# ringmod.net
KiCad netlist of a schematic drawn in EAGLE
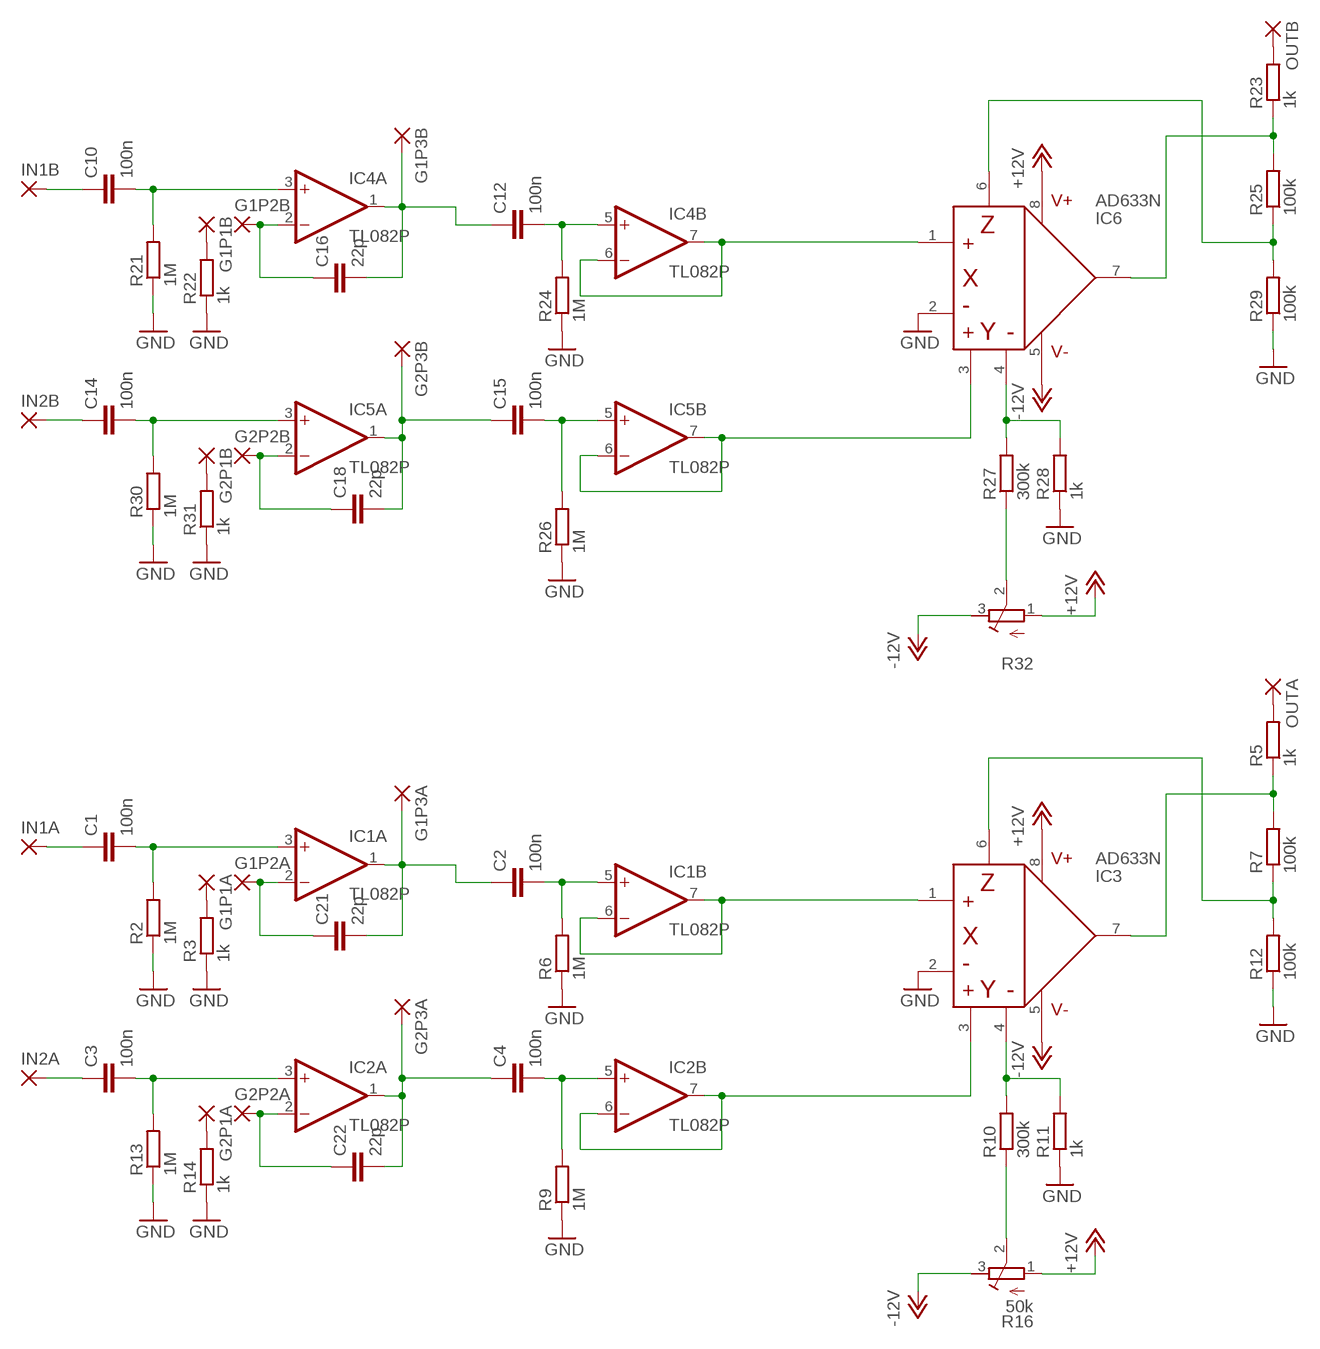
[diagram p0: schematic, sheet 1]
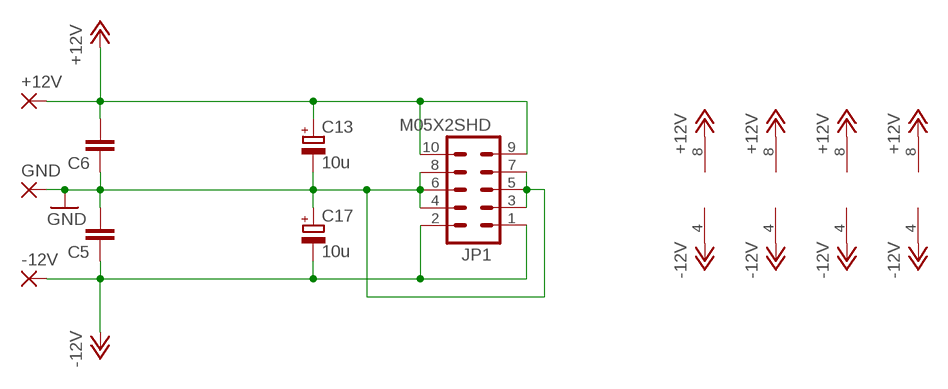
[diagram p1: schematic, sheet 2]

(export (version "E")
  (design (tool "Eeschema 10.0.6"))
  (components
    (comp (ref "C1")
      (value "100n")
      (footprint "eagle-import:C050-035X075")
      (libsource (lib "eagle-import") (part "C-EU050-035X075"))
    )
    (comp (ref "C2")
      (value "100n")
      (footprint "eagle-import:C050-035X075")
      (libsource (lib "eagle-import") (part "C-EU050-035X075"))
    )
    (comp (ref "C3")
      (value "100n")
      (footprint "eagle-import:C050-035X075")
      (libsource (lib "eagle-import") (part "C-EU050-035X075"))
    )
    (comp (ref "C4")
      (value "100n")
      (footprint "eagle-import:C050-035X075")
      (libsource (lib "eagle-import") (part "C-EU050-035X075"))
    )
    (comp (ref "C10")
      (value "100n")
      (footprint "eagle-import:C050-035X075")
      (libsource (lib "eagle-import") (part "C-EU050-035X075"))
    )
    (comp (ref "C12")
      (value "100n")
      (footprint "eagle-import:C050-035X075")
      (libsource (lib "eagle-import") (part "C-EU050-035X075"))
    )
    (comp (ref "C14")
      (value "100n")
      (footprint "eagle-import:C050-035X075")
      (libsource (lib "eagle-import") (part "C-EU050-035X075"))
    )
    (comp (ref "C15")
      (value "100n")
      (footprint "eagle-import:C050-035X075")
      (libsource (lib "eagle-import") (part "C-EU050-035X075"))
    )
    (comp (ref "C16")
      (value "22p")
      (footprint "eagle-import:C050-035X075")
      (libsource (lib "eagle-import") (part "C-EU050-035X075"))
    )
    (comp (ref "C18")
      (value "22p")
      (footprint "eagle-import:C050-035X075")
      (libsource (lib "eagle-import") (part "C-EU050-035X075"))
    )
    (comp (ref "C21")
      (value "22p")
      (footprint "eagle-import:C050-035X075")
      (libsource (lib "eagle-import") (part "C-EU050-035X075"))
    )
    (comp (ref "C22")
      (value "22p")
      (footprint "eagle-import:C050-035X075")
      (libsource (lib "eagle-import") (part "C-EU050-035X075"))
    )
    (comp (ref "G1P1A")
      (value "2,54/1,0")
      (footprint "eagle-import:2,54_1,0")
      (libsource (lib "eagle-import") (part "2,54/1,0"))
    )
    (comp (ref "G1P1B")
      (value "2,54/1,0")
      (footprint "eagle-import:2,54_1,0")
      (libsource (lib "eagle-import") (part "2,54/1,0"))
    )
    (comp (ref "G1P2A")
      (value "2,54/1,0")
      (footprint "eagle-import:2,54_1,0")
      (libsource (lib "eagle-import") (part "2,54/1,0"))
    )
    (comp (ref "G1P2B")
      (value "2,54/1,0")
      (footprint "eagle-import:2,54_1,0")
      (libsource (lib "eagle-import") (part "2,54/1,0"))
    )
    (comp (ref "G1P3A")
      (value "2,54/1,0")
      (footprint "eagle-import:2,54_1,0")
      (libsource (lib "eagle-import") (part "2,54/1,0"))
    )
    (comp (ref "G1P3B")
      (value "2,54/1,0")
      (footprint "eagle-import:2,54_1,0")
      (libsource (lib "eagle-import") (part "2,54/1,0"))
    )
    (comp (ref "G2P1A")
      (value "2,54/1,0")
      (footprint "eagle-import:2,54_1,0")
      (libsource (lib "eagle-import") (part "2,54/1,0"))
    )
    (comp (ref "G2P1B")
      (value "2,54/1,0")
      (footprint "eagle-import:2,54_1,0")
      (libsource (lib "eagle-import") (part "2,54/1,0"))
    )
    (comp (ref "G2P2A")
      (value "2,54/1,0")
      (footprint "eagle-import:2,54_1,0")
      (libsource (lib "eagle-import") (part "2,54/1,0"))
    )
    (comp (ref "G2P2B")
      (value "2,54/1,0")
      (footprint "eagle-import:2,54_1,0")
      (libsource (lib "eagle-import") (part "2,54/1,0"))
    )
    (comp (ref "G2P3A")
      (value "2,54/1,0")
      (footprint "eagle-import:2,54_1,0")
      (libsource (lib "eagle-import") (part "2,54/1,0"))
    )
    (comp (ref "G2P3B")
      (value "2,54/1,0")
      (footprint "eagle-import:2,54_1,0")
      (libsource (lib "eagle-import") (part "2,54/1,0"))
    )
    (comp (ref "IC1")
      (value "TL082P")
      (footprint "eagle-import:DIL08")
      (libsource (lib "eagle-import") (part "TL082P"))
    )
    (comp (ref "IC2")
      (value "TL082P")
      (footprint "eagle-import:DIL08")
      (libsource (lib "eagle-import") (part "TL082P"))
    )
    (comp (ref "IC3")
      (value "AD633N")
      (footprint "eagle-import:DIL08")
      (libsource (lib "eagle-import") (part "AD633N"))
    )
    (comp (ref "IC4")
      (value "TL082P")
      (footprint "eagle-import:DIL08")
      (libsource (lib "eagle-import") (part "TL082P"))
    )
    (comp (ref "IC5")
      (value "TL082P")
      (footprint "eagle-import:DIL08")
      (libsource (lib "eagle-import") (part "TL082P"))
    )
    (comp (ref "IC6")
      (value "AD633N")
      (footprint "eagle-import:DIL08")
      (libsource (lib "eagle-import") (part "AD633N"))
    )
    (comp (ref "IN1A")
      (value "2,54/1,0")
      (footprint "eagle-import:2,54_1,0")
      (libsource (lib "eagle-import") (part "2,54/1,0"))
    )
    (comp (ref "IN1B")
      (value "2,54/1,0")
      (footprint "eagle-import:2,54_1,0")
      (libsource (lib "eagle-import") (part "2,54/1,0"))
    )
    (comp (ref "IN2A")
      (value "2,54/1,0")
      (footprint "eagle-import:2,54_1,0")
      (libsource (lib "eagle-import") (part "2,54/1,0"))
    )
    (comp (ref "IN2B")
      (value "2,54/1,0")
      (footprint "eagle-import:2,54_1,0")
      (libsource (lib "eagle-import") (part "2,54/1,0"))
    )
    (comp (ref "OUTA")
      (value "2,54/1,0")
      (footprint "eagle-import:2,54_1,0")
      (libsource (lib "eagle-import") (part "2,54/1,0"))
    )
    (comp (ref "OUTB")
      (value "2,54/1,0")
      (footprint "eagle-import:2,54_1,0")
      (libsource (lib "eagle-import") (part "2,54/1,0"))
    )
    (comp (ref "R2")
      (value "1M")
      (footprint "eagle-import:0309_10")
      (libsource (lib "eagle-import") (part "R-EU_0309/10"))
    )
    (comp (ref "R3")
      (value "1k")
      (footprint "eagle-import:0309_10")
      (libsource (lib "eagle-import") (part "R-EU_0309/10"))
    )
    (comp (ref "R5")
      (value "1k")
      (footprint "eagle-import:0309_10")
      (libsource (lib "eagle-import") (part "R-EU_0309/10"))
    )
    (comp (ref "R6")
      (value "1M")
      (footprint "eagle-import:0309_10")
      (libsource (lib "eagle-import") (part "R-EU_0309/10"))
    )
    (comp (ref "R7")
      (value "100k")
      (footprint "eagle-import:0309_10")
      (libsource (lib "eagle-import") (part "R-EU_0309/10"))
    )
    (comp (ref "R9")
      (value "1M")
      (footprint "eagle-import:0309_10")
      (libsource (lib "eagle-import") (part "R-EU_0309/10"))
    )
    (comp (ref "R10")
      (value "300k")
      (footprint "eagle-import:0309_10")
      (libsource (lib "eagle-import") (part "R-EU_0309/10"))
    )
    (comp (ref "R11")
      (value "1k")
      (footprint "eagle-import:0309_10")
      (libsource (lib "eagle-import") (part "R-EU_0309/10"))
    )
    (comp (ref "R12")
      (value "100k")
      (footprint "eagle-import:0309_10")
      (libsource (lib "eagle-import") (part "R-EU_0309/10"))
    )
    (comp (ref "R13")
      (value "1M")
      (footprint "eagle-import:0309_10")
      (libsource (lib "eagle-import") (part "R-EU_0309/10"))
    )
    (comp (ref "R14")
      (value "1k")
      (footprint "eagle-import:0309_10")
      (libsource (lib "eagle-import") (part "R-EU_0309/10"))
    )
    (comp (ref "R16")
      (value "50k")
      (footprint "eagle-import:RTRIM64W")
      (libsource (lib "eagle-import") (part "R-TRIMM64W"))
    )
    (comp (ref "R21")
      (value "1M")
      (footprint "eagle-import:0309_10")
      (libsource (lib "eagle-import") (part "R-EU_0309/10"))
    )
    (comp (ref "R22")
      (value "1k")
      (footprint "eagle-import:0309_10")
      (libsource (lib "eagle-import") (part "R-EU_0309/10"))
    )
    (comp (ref "R23")
      (value "1k")
      (footprint "eagle-import:0309_10")
      (libsource (lib "eagle-import") (part "R-EU_0309/10"))
    )
    (comp (ref "R24")
      (value "1M")
      (footprint "eagle-import:0309_10")
      (libsource (lib "eagle-import") (part "R-EU_0309/10"))
    )
    (comp (ref "R25")
      (value "100k")
      (footprint "eagle-import:0309_10")
      (libsource (lib "eagle-import") (part "R-EU_0309/10"))
    )
    (comp (ref "R26")
      (value "1M")
      (footprint "eagle-import:0309_10")
      (libsource (lib "eagle-import") (part "R-EU_0309/10"))
    )
    (comp (ref "R27")
      (value "300k")
      (footprint "eagle-import:0309_10")
      (libsource (lib "eagle-import") (part "R-EU_0309/10"))
    )
    (comp (ref "R28")
      (value "1k")
      (footprint "eagle-import:0309_10")
      (libsource (lib "eagle-import") (part "R-EU_0309/10"))
    )
    (comp (ref "R29")
      (value "100k")
      (footprint "eagle-import:0309_10")
      (libsource (lib "eagle-import") (part "R-EU_0309/10"))
    )
    (comp (ref "R30")
      (value "1M")
      (footprint "eagle-import:0309_10")
      (libsource (lib "eagle-import") (part "R-EU_0309/10"))
    )
    (comp (ref "R31")
      (value "1k")
      (footprint "eagle-import:0309_10")
      (libsource (lib "eagle-import") (part "R-EU_0309/10"))
    )
    (comp (ref "R32")
      (value "R-TRIMM64W")
      (footprint "eagle-import:RTRIM64W")
      (libsource (lib "eagle-import") (part "R-TRIMM64W"))
    )
    (comp (ref "+12V")
      (value "2,54/1,0")
      (footprint "eagle-import:2,54_1,0")
      (libsource (lib "eagle-import") (part "2,54/1,0"))
    )
    (comp (ref "-12V")
      (value "2,54/1,0")
      (footprint "eagle-import:2,54_1,0")
      (libsource (lib "eagle-import") (part "2,54/1,0"))
    )
    (comp (ref "C5")
      (value "C-EU050-035X075")
      (footprint "eagle-import:C050-035X075")
      (libsource (lib "eagle-import") (part "C-EU050-035X075"))
    )
    (comp (ref "C6")
      (value "C-EU050-035X075")
      (footprint "eagle-import:C050-035X075")
      (libsource (lib "eagle-import") (part "C-EU050-035X075"))
    )
    (comp (ref "C13")
      (value "10u")
      (footprint "eagle-import:E3,5-8")
      (libsource (lib "eagle-import") (part "CPOL-EUE3.5-8"))
    )
    (comp (ref "C17")
      (value "10u")
      (footprint "eagle-import:E3,5-8")
      (libsource (lib "eagle-import") (part "CPOL-EUE3.5-8"))
    )
    (comp (ref "GND")
      (value "2,54/1,0")
      (footprint "eagle-import:2,54_1,0")
      (libsource (lib "eagle-import") (part "2,54/1,0"))
    )
    (comp (ref "JP1")
      (value "M05X2SHD")
      (footprint "eagle-import:2X5-SHROUDED")
      (libsource (lib "eagle-import") (part "M05X2SHD"))
    )
  )
  (nets
    (net (code "1") (name "+12V") (class "Default")
      (node (ref "+12V") (pin "1") (pinfunction "P_1") (pintype "passive"))
      (node (ref "C13") (pin "+") (pinfunction "+_+") (pintype "passive"))
      (node (ref "C6") (pin "2") (pinfunction "2_2") (pintype "passive"))
      (node (ref "IC1") (pin "8") (pinfunction "V+_8") (pintype "power_in"))
      (node (ref "IC2") (pin "8") (pinfunction "V+_8") (pintype "power_in"))
      (node (ref "IC3") (pin "8") (pinfunction "P$7_8") (pintype "power_in"))
      (node (ref "IC4") (pin "8") (pinfunction "V+_8") (pintype "power_in"))
      (node (ref "IC5") (pin "8") (pinfunction "V+_8") (pintype "power_in"))
      (node (ref "IC6") (pin "8") (pinfunction "P$7_8") (pintype "power_in"))
      (node (ref "JP1") (pin "10") (pinfunction "10_10") (pintype "passive"))
      (node (ref "JP1") (pin "9") (pinfunction "9_9") (pintype "passive"))
      (node (ref "R16") (pin "1") (pinfunction "A_1") (pintype "passive"))
      (node (ref "R32") (pin "1") (pinfunction "A_1") (pintype "passive"))
    )
    (net (code "2") (name "-12V") (class "Default")
      (node (ref "-12V") (pin "1") (pinfunction "P_1") (pintype "passive"))
      (node (ref "C17") (pin "-") (pinfunction "-_-") (pintype "passive"))
      (node (ref "C5") (pin "1") (pinfunction "1_1") (pintype "passive"))
      (node (ref "IC1") (pin "4") (pinfunction "V-_4") (pintype "power_in"))
      (node (ref "IC2") (pin "4") (pinfunction "V-_4") (pintype "power_in"))
      (node (ref "IC3") (pin "5") (pinfunction "P$8_5") (pintype "power_in"))
      (node (ref "IC4") (pin "4") (pinfunction "V-_4") (pintype "power_in"))
      (node (ref "IC5") (pin "4") (pinfunction "V-_4") (pintype "power_in"))
      (node (ref "IC6") (pin "5") (pinfunction "P$8_5") (pintype "power_in"))
      (node (ref "JP1") (pin "1") (pinfunction "1_1") (pintype "passive"))
      (node (ref "JP1") (pin "2") (pinfunction "2_2") (pintype "passive"))
      (node (ref "R16") (pin "3") (pinfunction "E_3") (pintype "passive"))
      (node (ref "R32") (pin "3") (pinfunction "E_3") (pintype "passive"))
    )
    (net (code "3") (name "GND") (class "Default")
      (node (ref "C13") (pin "-") (pinfunction "-_-") (pintype "passive"))
      (node (ref "C17") (pin "+") (pinfunction "+_+") (pintype "passive"))
      (node (ref "C5") (pin "2") (pinfunction "2_2") (pintype "passive"))
      (node (ref "C6") (pin "1") (pinfunction "1_1") (pintype "passive"))
      (node (ref "GND") (pin "1") (pinfunction "P_1") (pintype "passive"))
      (node (ref "IC3") (pin "2") (pinfunction "P$2_2") (pintype "bidirectional"))
      (node (ref "IC6") (pin "2") (pinfunction "P$2_2") (pintype "bidirectional"))
      (node (ref "JP1") (pin "3") (pinfunction "3_3") (pintype "passive"))
      (node (ref "JP1") (pin "4") (pinfunction "4_4") (pintype "passive"))
      (node (ref "JP1") (pin "5") (pinfunction "5_5") (pintype "passive"))
      (node (ref "JP1") (pin "6") (pinfunction "6_6") (pintype "passive"))
      (node (ref "JP1") (pin "7") (pinfunction "7_7") (pintype "passive"))
      (node (ref "JP1") (pin "8") (pinfunction "8_8") (pintype "passive"))
      (node (ref "R11") (pin "1") (pinfunction "1_1") (pintype "passive"))
      (node (ref "R12") (pin "1") (pinfunction "1_1") (pintype "passive"))
      (node (ref "R13") (pin "1") (pinfunction "1_1") (pintype "passive"))
      (node (ref "R14") (pin "1") (pinfunction "1_1") (pintype "passive"))
      (node (ref "R2") (pin "1") (pinfunction "1_1") (pintype "passive"))
      (node (ref "R21") (pin "1") (pinfunction "1_1") (pintype "passive"))
      (node (ref "R22") (pin "1") (pinfunction "1_1") (pintype "passive"))
      (node (ref "R24") (pin "1") (pinfunction "1_1") (pintype "passive"))
      (node (ref "R26") (pin "1") (pinfunction "1_1") (pintype "passive"))
      (node (ref "R28") (pin "1") (pinfunction "1_1") (pintype "passive"))
      (node (ref "R29") (pin "1") (pinfunction "1_1") (pintype "passive"))
      (node (ref "R3") (pin "1") (pinfunction "1_1") (pintype "passive"))
      (node (ref "R30") (pin "1") (pinfunction "1_1") (pintype "passive"))
      (node (ref "R31") (pin "1") (pinfunction "1_1") (pintype "passive"))
      (node (ref "R6") (pin "1") (pinfunction "1_1") (pintype "passive"))
      (node (ref "R9") (pin "1") (pinfunction "1_1") (pintype "passive"))
    )
    (net (code "4") (name "Net-(G1P1A-P)") (class "Default")
      (node (ref "G1P1A") (pin "1") (pinfunction "P_1") (pintype "passive"))
      (node (ref "R3") (pin "2") (pinfunction "2_2") (pintype "passive"))
    )
    (net (code "5") (name "Net-(G1P1B-P)") (class "Default")
      (node (ref "G1P1B") (pin "1") (pinfunction "P_1") (pintype "passive"))
      (node (ref "R22") (pin "2") (pinfunction "2_2") (pintype "passive"))
    )
    (net (code "6") (name "Net-(G1P2A-P)") (class "Default")
      (node (ref "C21") (pin "1") (pinfunction "1_1") (pintype "passive"))
      (node (ref "G1P2A") (pin "1") (pinfunction "P_1") (pintype "passive"))
      (node (ref "IC1") (pin "2") (pinfunction "-IN_2") (pintype "input"))
    )
    (net (code "7") (name "Net-(G1P2B-P)") (class "Default")
      (node (ref "C16") (pin "1") (pinfunction "1_1") (pintype "passive"))
      (node (ref "G1P2B") (pin "1") (pinfunction "P_1") (pintype "passive"))
      (node (ref "IC4") (pin "2") (pinfunction "-IN_2") (pintype "input"))
    )
    (net (code "8") (name "Net-(G1P3A-P)") (class "Default")
      (node (ref "C2") (pin "1") (pinfunction "1_1") (pintype "passive"))
      (node (ref "C21") (pin "2") (pinfunction "2_2") (pintype "passive"))
      (node (ref "G1P3A") (pin "1") (pinfunction "P_1") (pintype "passive"))
      (node (ref "IC1") (pin "1") (pinfunction "OUT_1") (pintype "output"))
    )
    (net (code "9") (name "Net-(G1P3B-P)") (class "Default")
      (node (ref "C12") (pin "1") (pinfunction "1_1") (pintype "passive"))
      (node (ref "C16") (pin "2") (pinfunction "2_2") (pintype "passive"))
      (node (ref "G1P3B") (pin "1") (pinfunction "P_1") (pintype "passive"))
      (node (ref "IC4") (pin "1") (pinfunction "OUT_1") (pintype "output"))
    )
    (net (code "10") (name "Net-(G2P1A-P)") (class "Default")
      (node (ref "G2P1A") (pin "1") (pinfunction "P_1") (pintype "passive"))
      (node (ref "R14") (pin "2") (pinfunction "2_2") (pintype "passive"))
    )
    (net (code "11") (name "Net-(G2P1B-P)") (class "Default")
      (node (ref "G2P1B") (pin "1") (pinfunction "P_1") (pintype "passive"))
      (node (ref "R31") (pin "2") (pinfunction "2_2") (pintype "passive"))
    )
    (net (code "12") (name "Net-(G2P2A-P)") (class "Default")
      (node (ref "C22") (pin "1") (pinfunction "1_1") (pintype "passive"))
      (node (ref "G2P2A") (pin "1") (pinfunction "P_1") (pintype "passive"))
      (node (ref "IC2") (pin "2") (pinfunction "-IN_2") (pintype "input"))
    )
    (net (code "13") (name "Net-(G2P2B-P)") (class "Default")
      (node (ref "C18") (pin "1") (pinfunction "1_1") (pintype "passive"))
      (node (ref "G2P2B") (pin "1") (pinfunction "P_1") (pintype "passive"))
      (node (ref "IC5") (pin "2") (pinfunction "-IN_2") (pintype "input"))
    )
    (net (code "14") (name "Net-(G2P3A-P)") (class "Default")
      (node (ref "C22") (pin "2") (pinfunction "2_2") (pintype "passive"))
      (node (ref "C4") (pin "1") (pinfunction "1_1") (pintype "passive"))
      (node (ref "G2P3A") (pin "1") (pinfunction "P_1") (pintype "passive"))
      (node (ref "IC2") (pin "1") (pinfunction "OUT_1") (pintype "output"))
    )
    (net (code "15") (name "Net-(G2P3B-P)") (class "Default")
      (node (ref "C15") (pin "1") (pinfunction "1_1") (pintype "passive"))
      (node (ref "C18") (pin "2") (pinfunction "2_2") (pintype "passive"))
      (node (ref "G2P3B") (pin "1") (pinfunction "P_1") (pintype "passive"))
      (node (ref "IC5") (pin "1") (pinfunction "OUT_1") (pintype "output"))
    )
    (net (code "16") (name "Net-(IC1A-+IN)") (class "Default")
      (node (ref "C1") (pin "2") (pinfunction "2_2") (pintype "passive"))
      (node (ref "IC1") (pin "3") (pinfunction "+IN_3") (pintype "input"))
      (node (ref "R2") (pin "2") (pinfunction "2_2") (pintype "passive"))
    )
    (net (code "17") (name "Net-(IC1B-+IN)") (class "Default")
      (node (ref "C2") (pin "2") (pinfunction "2_2") (pintype "passive"))
      (node (ref "IC1") (pin "5") (pinfunction "+IN_5") (pintype "input"))
      (node (ref "R6") (pin "2") (pinfunction "2_2") (pintype "passive"))
    )
    (net (code "18") (name "Net-(IC1B--IN)") (class "Default")
      (node (ref "IC1") (pin "6") (pinfunction "-IN_6") (pintype "input"))
      (node (ref "IC1") (pin "7") (pinfunction "OUT_7") (pintype "output"))
      (node (ref "IC3") (pin "1") (pinfunction "P$1_1") (pintype "bidirectional"))
    )
    (net (code "19") (name "Net-(IC2A-+IN)") (class "Default")
      (node (ref "C3") (pin "2") (pinfunction "2_2") (pintype "passive"))
      (node (ref "IC2") (pin "3") (pinfunction "+IN_3") (pintype "input"))
      (node (ref "R13") (pin "2") (pinfunction "2_2") (pintype "passive"))
    )
    (net (code "20") (name "Net-(IC2B-+IN)") (class "Default")
      (node (ref "C4") (pin "2") (pinfunction "2_2") (pintype "passive"))
      (node (ref "IC2") (pin "5") (pinfunction "+IN_5") (pintype "input"))
      (node (ref "R9") (pin "2") (pinfunction "2_2") (pintype "passive"))
    )
    (net (code "21") (name "Net-(IC2B--IN)") (class "Default")
      (node (ref "IC2") (pin "6") (pinfunction "-IN_6") (pintype "input"))
      (node (ref "IC2") (pin "7") (pinfunction "OUT_7") (pintype "output"))
      (node (ref "IC3") (pin "3") (pinfunction "P$3_3") (pintype "bidirectional"))
    )
    (net (code "22") (name "Net-(IC3-P$4)") (class "Default")
      (node (ref "IC3") (pin "4") (pinfunction "P$4_4") (pintype "bidirectional"))
      (node (ref "R10") (pin "2") (pinfunction "2_2") (pintype "passive"))
      (node (ref "R11") (pin "2") (pinfunction "2_2") (pintype "passive"))
    )
    (net (code "23") (name "Net-(IC3-P$5)") (class "Default")
      (node (ref "IC3") (pin "6") (pinfunction "P$5_6") (pintype "bidirectional"))
      (node (ref "R12") (pin "2") (pinfunction "2_2") (pintype "passive"))
      (node (ref "R7") (pin "1") (pinfunction "1_1") (pintype "passive"))
    )
    (net (code "24") (name "Net-(IC3-P$6)") (class "Default")
      (node (ref "IC3") (pin "7") (pinfunction "P$6_7") (pintype "bidirectional"))
      (node (ref "R5") (pin "1") (pinfunction "1_1") (pintype "passive"))
      (node (ref "R7") (pin "2") (pinfunction "2_2") (pintype "passive"))
    )
    (net (code "25") (name "Net-(IC4A-+IN)") (class "Default")
      (node (ref "C10") (pin "2") (pinfunction "2_2") (pintype "passive"))
      (node (ref "IC4") (pin "3") (pinfunction "+IN_3") (pintype "input"))
      (node (ref "R21") (pin "2") (pinfunction "2_2") (pintype "passive"))
    )
    (net (code "26") (name "Net-(IC4B-+IN)") (class "Default")
      (node (ref "C12") (pin "2") (pinfunction "2_2") (pintype "passive"))
      (node (ref "IC4") (pin "5") (pinfunction "+IN_5") (pintype "input"))
      (node (ref "R24") (pin "2") (pinfunction "2_2") (pintype "passive"))
    )
    (net (code "27") (name "Net-(IC4B--IN)") (class "Default")
      (node (ref "IC4") (pin "6") (pinfunction "-IN_6") (pintype "input"))
      (node (ref "IC4") (pin "7") (pinfunction "OUT_7") (pintype "output"))
      (node (ref "IC6") (pin "1") (pinfunction "P$1_1") (pintype "bidirectional"))
    )
    (net (code "28") (name "Net-(IC5A-+IN)") (class "Default")
      (node (ref "C14") (pin "2") (pinfunction "2_2") (pintype "passive"))
      (node (ref "IC5") (pin "3") (pinfunction "+IN_3") (pintype "input"))
      (node (ref "R30") (pin "2") (pinfunction "2_2") (pintype "passive"))
    )
    (net (code "29") (name "Net-(IC5B-+IN)") (class "Default")
      (node (ref "C15") (pin "2") (pinfunction "2_2") (pintype "passive"))
      (node (ref "IC5") (pin "5") (pinfunction "+IN_5") (pintype "input"))
      (node (ref "R26") (pin "2") (pinfunction "2_2") (pintype "passive"))
    )
    (net (code "30") (name "Net-(IC5B--IN)") (class "Default")
      (node (ref "IC5") (pin "6") (pinfunction "-IN_6") (pintype "input"))
      (node (ref "IC5") (pin "7") (pinfunction "OUT_7") (pintype "output"))
      (node (ref "IC6") (pin "3") (pinfunction "P$3_3") (pintype "bidirectional"))
    )
    (net (code "31") (name "Net-(IC6-P$4)") (class "Default")
      (node (ref "IC6") (pin "4") (pinfunction "P$4_4") (pintype "bidirectional"))
      (node (ref "R27") (pin "2") (pinfunction "2_2") (pintype "passive"))
      (node (ref "R28") (pin "2") (pinfunction "2_2") (pintype "passive"))
    )
    (net (code "32") (name "Net-(IC6-P$5)") (class "Default")
      (node (ref "IC6") (pin "6") (pinfunction "P$5_6") (pintype "bidirectional"))
      (node (ref "R25") (pin "1") (pinfunction "1_1") (pintype "passive"))
      (node (ref "R29") (pin "2") (pinfunction "2_2") (pintype "passive"))
    )
    (net (code "33") (name "Net-(IC6-P$6)") (class "Default")
      (node (ref "IC6") (pin "7") (pinfunction "P$6_7") (pintype "bidirectional"))
      (node (ref "R23") (pin "1") (pinfunction "1_1") (pintype "passive"))
      (node (ref "R25") (pin "2") (pinfunction "2_2") (pintype "passive"))
    )
    (net (code "34") (name "Net-(IN1A-P)") (class "Default")
      (node (ref "C1") (pin "1") (pinfunction "1_1") (pintype "passive"))
      (node (ref "IN1A") (pin "1") (pinfunction "P_1") (pintype "passive"))
    )
    (net (code "35") (name "Net-(IN1B-P)") (class "Default")
      (node (ref "C10") (pin "1") (pinfunction "1_1") (pintype "passive"))
      (node (ref "IN1B") (pin "1") (pinfunction "P_1") (pintype "passive"))
    )
    (net (code "36") (name "Net-(IN2A-P)") (class "Default")
      (node (ref "C3") (pin "1") (pinfunction "1_1") (pintype "passive"))
      (node (ref "IN2A") (pin "1") (pinfunction "P_1") (pintype "passive"))
    )
    (net (code "37") (name "Net-(IN2B-P)") (class "Default")
      (node (ref "C14") (pin "1") (pinfunction "1_1") (pintype "passive"))
      (node (ref "IN2B") (pin "1") (pinfunction "P_1") (pintype "passive"))
    )
    (net (code "38") (name "Net-(OUTA-P)") (class "Default")
      (node (ref "OUTA") (pin "1") (pinfunction "P_1") (pintype "passive"))
      (node (ref "R5") (pin "2") (pinfunction "2_2") (pintype "passive"))
    )
    (net (code "39") (name "Net-(OUTB-P)") (class "Default")
      (node (ref "OUTB") (pin "1") (pinfunction "P_1") (pintype "passive"))
      (node (ref "R23") (pin "2") (pinfunction "2_2") (pintype "passive"))
    )
    (net (code "40") (name "Net-(R16-S)") (class "Default")
      (node (ref "R10") (pin "1") (pinfunction "1_1") (pintype "passive"))
      (node (ref "R16") (pin "2") (pinfunction "S_2") (pintype "passive"))
    )
    (net (code "41") (name "Net-(R32-S)") (class "Default")
      (node (ref "R27") (pin "1") (pinfunction "1_1") (pintype "passive"))
      (node (ref "R32") (pin "2") (pinfunction "S_2") (pintype "passive"))
    )
  )
)
